# SCH_task1_2026-04-27.net
KiCad netlist of a schematic drawn in EasyEDA
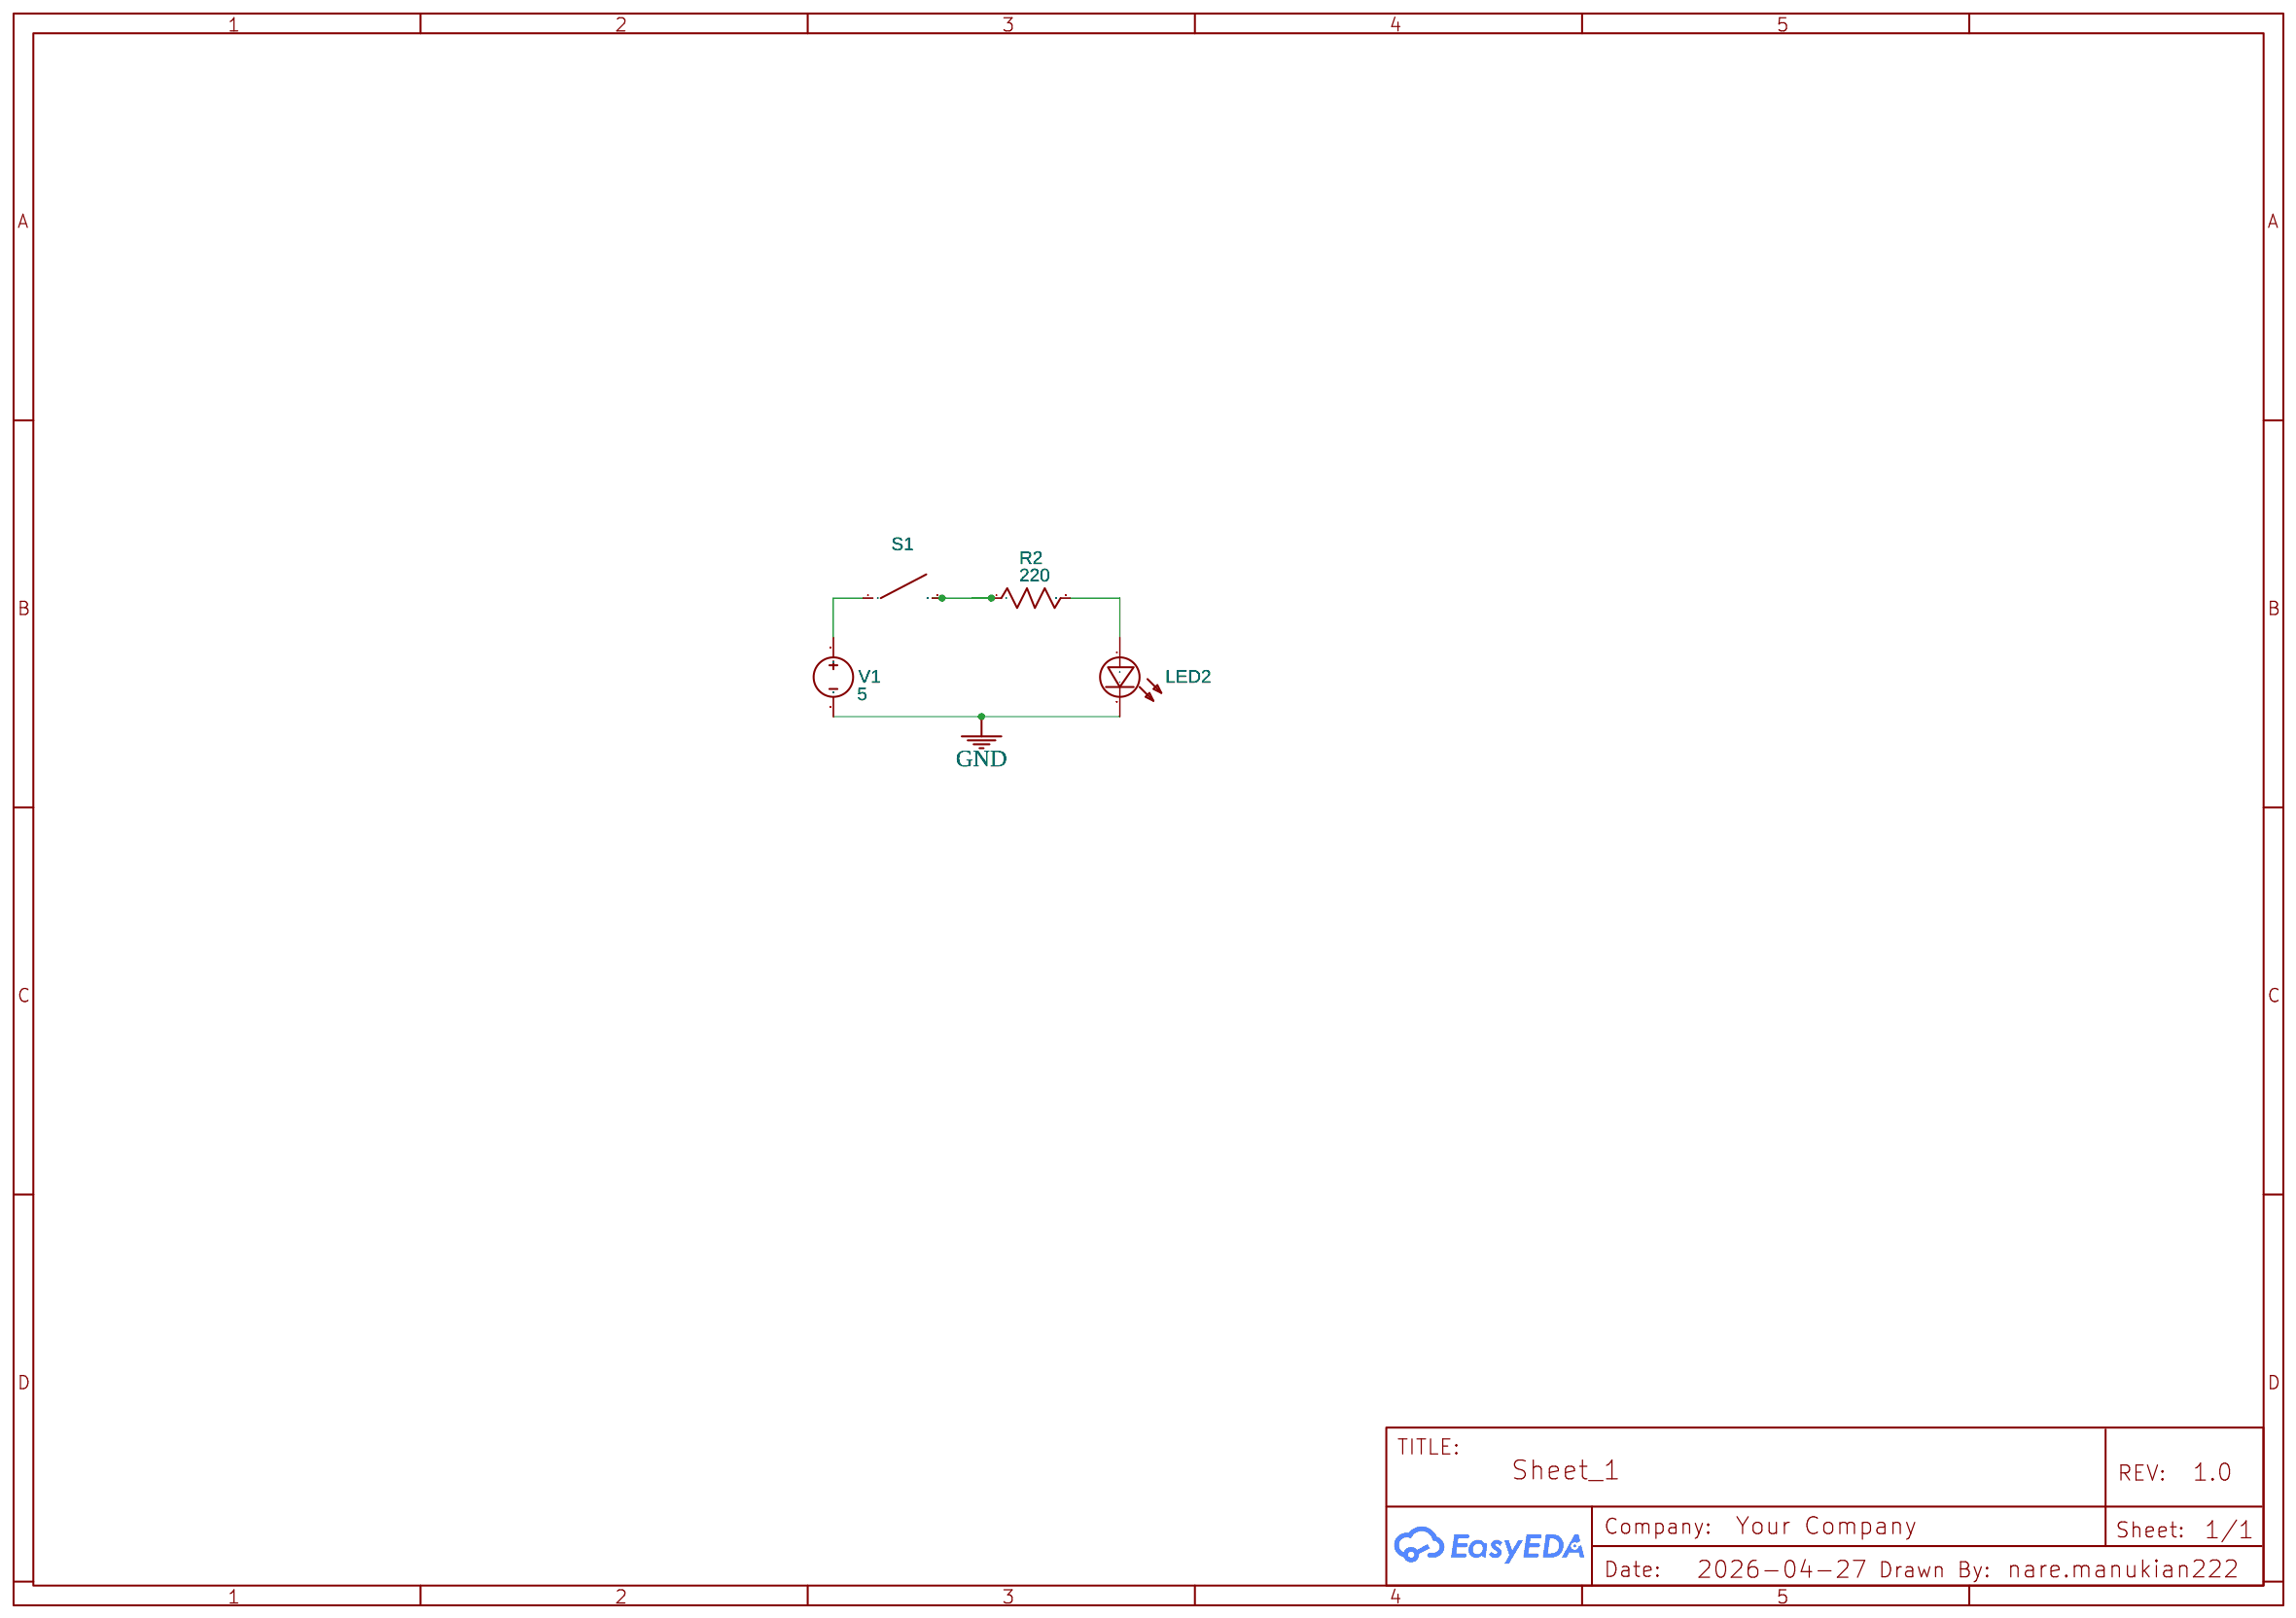
[diagram p0: schematic sheet]

(export (version "E")
  (design (tool "Eeschema 10.0.6"))
  (components
    (comp (ref "LED2") (value "LED") (libsource (lib "") (part "LED")))
    (comp (ref "R2") (value "220") (libsource (lib "") (part "Resistor_US")))
    (comp (ref "S1") (value "SPST_Open") (libsource (lib "") (part "SPST")))
    (comp (ref "V1") (value "5") (libsource (lib "") (part "VDC")))
  )
  (nets
    (net (code "1") (name "GND") (class "Default")
      (node (ref "LED2") (pin "2") (pinfunction "-_2") (pintype "unspecified"))
      (node (ref "V1") (pin "2") (pinfunction "2_2") (pintype "unspecified"))
    )
    (net (code "2") (name "Net-(LED2-+)") (class "Default")
      (node (ref "LED2") (pin "1") (pinfunction "+_1") (pintype "unspecified"))
      (node (ref "R2") (pin "2") (pinfunction "2_2") (pintype "unspecified"))
    )
    (net (code "3") (name "Net-(R2-Pad1)") (class "Default")
      (node (ref "R2") (pin "1") (pinfunction "1_1") (pintype "unspecified"))
      (node (ref "S1") (pin "2") (pinfunction "2_2") (pintype "unspecified"))
    )
    (net (code "4") (name "Net-(S1-Pad1)") (class "Default")
      (node (ref "S1") (pin "1") (pinfunction "1_1") (pintype "unspecified"))
      (node (ref "V1") (pin "1") (pinfunction "1_1") (pintype "unspecified"))
    )
  )
)
